# Accelerometer.net
KiCad netlist of a schematic drawn in Altium Designer
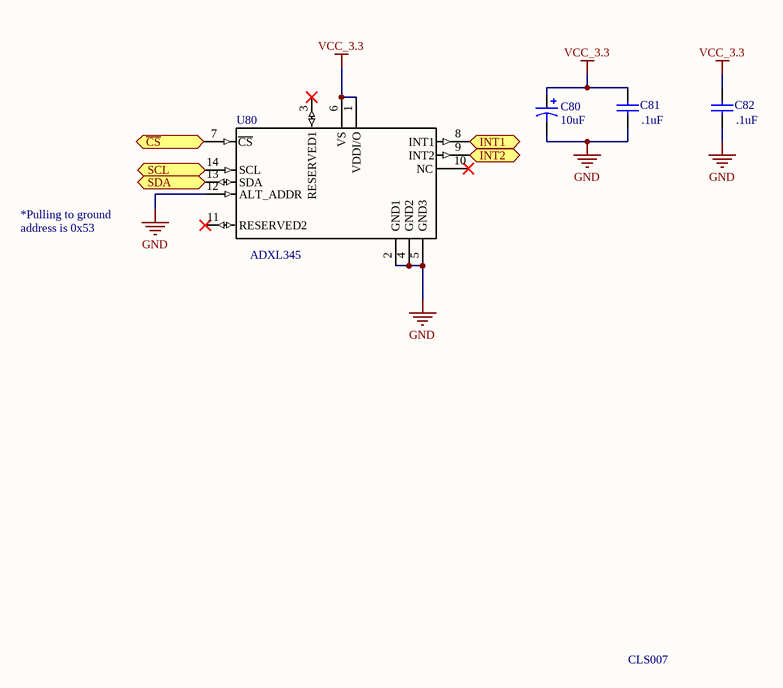
[diagram p0: Accelerometer.SchDoc]

(export (version "E")
  (design (tool "Eeschema 10.0.6"))
  (components
    (comp (ref "C80")
      (value "10uF")
      (footprint "0805_CHIP_FP")
      (fields
        (field (name "MANUFACTURER") "AVX Corporation")
        (field (name "MANUFACTURER PART NUMBER") "TLJR106M010R3000")
        (field (name "VENDOR PART NUMBER") "478-3346-1-ND")
      )
      (libsource (lib "GenericSymbols") (part "Capacitor Polarized"))
    )
    (comp (ref "C81")
      (value ".1uF")
      (footprint "0805_CHIP_FP")
      (fields
        (field (name "MANUFACTURER") "Johanson Dielectrics Inc.")
        (field (name "MANUFACTURER PART NUMBER") "250R15W104KV4T")
        (field (name "VENDOR PART NUMBER") "709-1185-1-ND")
      )
      (libsource (lib "GenericSymbols") (part "Capacitor_unpolarized_0805"))
    )
    (comp (ref "C82")
      (value ".1uF")
      (footprint "0805_CHIP_FP")
      (fields
        (field (name "MANUFACTURER") "Johanson Dielectrics Inc.")
        (field (name "MANUFACTURER PART NUMBER") "250R15W104KV4T")
        (field (name "VENDOR PART NUMBER") "709-1185-1-ND")
      )
      (libsource (lib "GenericSymbols") (part "Capacitor_unpolarized_0805"))
    )
    (comp (ref "U80")
      (value "MOTION/POSITION-ADXL345BCCZ-RL(14P-5.0X3.0MM)")
      (footprint "ADI-CC-14-1_V")
      (description "Accelerometer Triple Â±2/Â±4/Â±8/Â±16g 2V to 3.6V 14-Pin LGA T/R")
      (fields
        (field (name "MANUFACTURER") "Analog Devices Inc.")
        (field (name "MANUFACTURER PART NUMBER") "ADXL345BCCZ-RL")
      )
      (libsource (lib "MOTION_POSITION-ADXL345BCCZ-RL_14P-5.0X3.0MM_") (part "MOTION/POSITION-ADXL345BCCZ-RL(14P-5.0X3.0MM)"))
    )
  )
  (nets
    (net (code "1") (name "/INT1") (class "Default")
      (node (ref "U80") (pin "8") (pinfunction "INT1_8") (pintype "output"))
    )
    (net (code "2") (name "/INT2") (class "Default")
      (node (ref "U80") (pin "9") (pinfunction "INT2_9") (pintype "output"))
    )
    (net (code "3") (name "/SCL") (class "Default")
      (node (ref "U80") (pin "14") (pinfunction "SCL_14") (pintype "input"))
    )
    (net (code "4") (name "/SDA") (class "Default")
      (node (ref "U80") (pin "13") (pinfunction "SDA_13") (pintype "bidirectional"))
    )
    (net (code "5") (name "/~{CS}") (class "Default")
      (node (ref "U80") (pin "7") (pinfunction "~{CS}_7") (pintype "input"))
    )
    (net (code "6") (name "GND") (class "Default")
      (node (ref "C80") (pin "2") (pinfunction "2_2") (pintype "passive"))
      (node (ref "C81") (pin "1") (pinfunction "1_1") (pintype "passive"))
      (node (ref "C82") (pin "1") (pinfunction "1_1") (pintype "passive"))
      (node (ref "U80") (pin "12") (pinfunction "ALT_ADDR_12") (pintype "input"))
      (node (ref "U80") (pin "2") (pinfunction "GND1_2") (pintype "power_in"))
      (node (ref "U80") (pin "4") (pinfunction "GND2_4") (pintype "power_in"))
      (node (ref "U80") (pin "5") (pinfunction "GND3_5") (pintype "power_in"))
    )
    (net (code "7") (name "VCC_3.3") (class "Default")
      (node (ref "C80") (pin "1") (pinfunction "1_1") (pintype "passive"))
      (node (ref "C81") (pin "2") (pinfunction "2_2") (pintype "passive"))
      (node (ref "C82") (pin "2") (pinfunction "2_2") (pintype "passive"))
      (node (ref "U80") (pin "1") (pinfunction "VDDI/O_1") (pintype "power_in"))
      (node (ref "U80") (pin "6") (pinfunction "VS_6") (pintype "power_in"))
    )
    (net (code "8") (name "unconnected-(U80-NC-Pad10)") (class "Default")
      (node (ref "U80") (pin "10") (pinfunction "NC_10") (pintype "passive+no_connect"))
    )
    (net (code "9") (name "unconnected-(U80-RESERVED1-Pad3)") (class "Default")
      (node (ref "U80") (pin "3") (pinfunction "RESERVED1_3") (pintype "bidirectional+no_connect"))
    )
    (net (code "10") (name "unconnected-(U80-RESERVED2-Pad11)") (class "Default")
      (node (ref "U80") (pin "11") (pinfunction "RESERVED2_11") (pintype "bidirectional+no_connect"))
    )
  )
)
